# transformer.net
KiCad netlist of a schematic drawn in Altium Designer
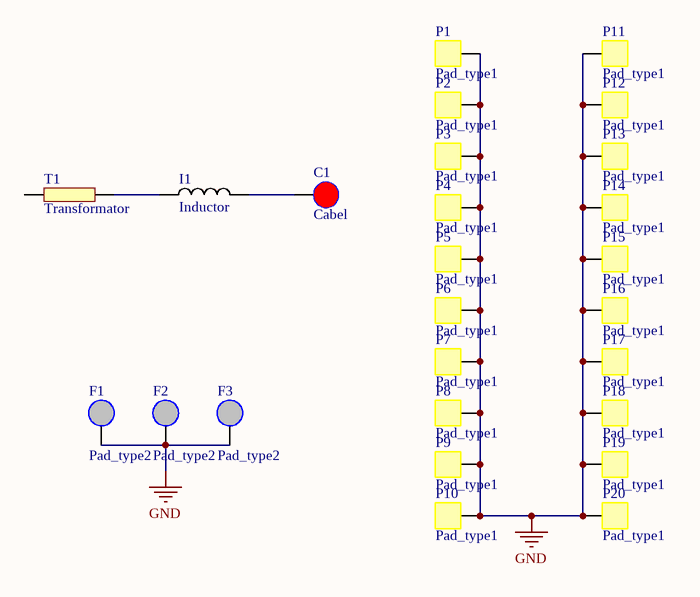
[diagram p0: transformer.SchDoc]

(export (version "E")
  (design (tool "Eeschema 10.0.6"))
  (components
    (comp (ref "C1")
      (value "Cabel")
      (footprint "transformerLib:pad_type3")
      (libsource (lib "transformerLib") (part "Cabel"))
    )
    (comp (ref "F1")
      (value "Pad_type2")
      (footprint "transformerLib:pad_type2")
      (libsource (lib "transformerLib") (part "Pad_type2"))
    )
    (comp (ref "F2")
      (value "Pad_type2")
      (footprint "transformerLib:pad_type2")
      (libsource (lib "transformerLib") (part "Pad_type2"))
    )
    (comp (ref "F3")
      (value "Pad_type2")
      (footprint "transformerLib:pad_type2")
      (libsource (lib "transformerLib") (part "Pad_type2"))
    )
    (comp (ref "I1")
      (value "Inductor")
      (footprint "transformerLib:Inductor")
      (libsource (lib "transformerLib") (part "Inductor"))
    )
    (comp (ref "P1")
      (value "Pad_type1")
      (footprint "transformerLib:pad_type1")
      (libsource (lib "transformerLib") (part "Pad_type1"))
    )
    (comp (ref "P2")
      (value "Pad_type1")
      (footprint "transformerLib:pad_type1")
      (libsource (lib "transformerLib") (part "Pad_type1"))
    )
    (comp (ref "P3")
      (value "Pad_type1")
      (footprint "transformerLib:pad_type1")
      (libsource (lib "transformerLib") (part "Pad_type1"))
    )
    (comp (ref "P4")
      (value "Pad_type1")
      (footprint "transformerLib:pad_type1")
      (libsource (lib "transformerLib") (part "Pad_type1"))
    )
    (comp (ref "P5")
      (value "Pad_type1")
      (footprint "transformerLib:pad_type1")
      (libsource (lib "transformerLib") (part "Pad_type1"))
    )
    (comp (ref "P6")
      (value "Pad_type1")
      (footprint "transformerLib:pad_type1")
      (libsource (lib "transformerLib") (part "Pad_type1"))
    )
    (comp (ref "P7")
      (value "Pad_type1")
      (footprint "transformerLib:pad_type1")
      (libsource (lib "transformerLib") (part "Pad_type1"))
    )
    (comp (ref "P8")
      (value "Pad_type1")
      (footprint "transformerLib:pad_type1")
      (libsource (lib "transformerLib") (part "Pad_type1"))
    )
    (comp (ref "P9")
      (value "Pad_type1")
      (footprint "transformerLib:pad_type1")
      (libsource (lib "transformerLib") (part "Pad_type1"))
    )
    (comp (ref "P10")
      (value "Pad_type1")
      (footprint "transformerLib:pad_type1")
      (libsource (lib "transformerLib") (part "Pad_type1"))
    )
    (comp (ref "P11")
      (value "Pad_type1")
      (footprint "transformerLib:pad_type1")
      (libsource (lib "") (part "Pad_type1_1"))
    )
    (comp (ref "P12")
      (value "Pad_type1")
      (footprint "transformerLib:pad_type1")
      (libsource (lib "") (part "Pad_type1_1"))
    )
    (comp (ref "P13")
      (value "Pad_type1")
      (footprint "transformerLib:pad_type1")
      (libsource (lib "") (part "Pad_type1_1"))
    )
    (comp (ref "P14")
      (value "Pad_type1")
      (footprint "transformerLib:pad_type1")
      (libsource (lib "") (part "Pad_type1_1"))
    )
    (comp (ref "P15")
      (value "Pad_type1")
      (footprint "transformerLib:pad_type1")
      (libsource (lib "") (part "Pad_type1_1"))
    )
    (comp (ref "P16")
      (value "Pad_type1")
      (footprint "transformerLib:pad_type1")
      (libsource (lib "") (part "Pad_type1_1"))
    )
    (comp (ref "P17")
      (value "Pad_type1")
      (footprint "transformerLib:pad_type1")
      (libsource (lib "") (part "Pad_type1_1"))
    )
    (comp (ref "P18")
      (value "Pad_type1")
      (footprint "transformerLib:pad_type1")
      (libsource (lib "") (part "Pad_type1_1"))
    )
    (comp (ref "P19")
      (value "Pad_type1")
      (footprint "transformerLib:pad_type1")
      (libsource (lib "") (part "Pad_type1_1"))
    )
    (comp (ref "P20")
      (value "Pad_type1")
      (footprint "transformerLib:pad_type1")
      (libsource (lib "") (part "Pad_type1_1"))
    )
    (comp (ref "T1")
      (value "Transformator")
      (footprint "transformerLib:tr_all")
      (libsource (lib "transformerLib") (part "Transformator"))
    )
  )
  (nets
    (net (code "1") (name "GND") (class "Default")
      (node (ref "F1") (pin "1") (pinfunction "1_1") (pintype "passive"))
      (node (ref "F2") (pin "1") (pinfunction "1_1") (pintype "passive"))
      (node (ref "F3") (pin "1") (pinfunction "1_1") (pintype "passive"))
      (node (ref "P1") (pin "1") (pinfunction "1_1") (pintype "passive"))
      (node (ref "P10") (pin "1") (pinfunction "1_1") (pintype "passive"))
      (node (ref "P11") (pin "1") (pinfunction "1_1") (pintype "passive"))
      (node (ref "P12") (pin "1") (pinfunction "1_1") (pintype "passive"))
      (node (ref "P13") (pin "1") (pinfunction "1_1") (pintype "passive"))
      (node (ref "P14") (pin "1") (pinfunction "1_1") (pintype "passive"))
      (node (ref "P15") (pin "1") (pinfunction "1_1") (pintype "passive"))
      (node (ref "P16") (pin "1") (pinfunction "1_1") (pintype "passive"))
      (node (ref "P17") (pin "1") (pinfunction "1_1") (pintype "passive"))
      (node (ref "P18") (pin "1") (pinfunction "1_1") (pintype "passive"))
      (node (ref "P19") (pin "1") (pinfunction "1_1") (pintype "passive"))
      (node (ref "P2") (pin "1") (pinfunction "1_1") (pintype "passive"))
      (node (ref "P20") (pin "1") (pinfunction "1_1") (pintype "passive"))
      (node (ref "P3") (pin "1") (pinfunction "1_1") (pintype "passive"))
      (node (ref "P4") (pin "1") (pinfunction "1_1") (pintype "passive"))
      (node (ref "P5") (pin "1") (pinfunction "1_1") (pintype "passive"))
      (node (ref "P6") (pin "1") (pinfunction "1_1") (pintype "passive"))
      (node (ref "P7") (pin "1") (pinfunction "1_1") (pintype "passive"))
      (node (ref "P8") (pin "1") (pinfunction "1_1") (pintype "passive"))
      (node (ref "P9") (pin "1") (pinfunction "1_1") (pintype "passive"))
    )
    (net (code "2") (name "Net-(C1-Pad1)") (class "Default")
      (node (ref "C1") (pin "1") (pinfunction "1_1") (pintype "passive"))
      (node (ref "I1") (pin "2") (pinfunction "2_2") (pintype "passive"))
    )
    (net (code "3") (name "Net-(I1-Pad1)") (class "Default")
      (node (ref "I1") (pin "1") (pinfunction "1_1") (pintype "passive"))
      (node (ref "T1") (pin "2") (pinfunction "2_2") (pintype "passive"))
    )
    (net (code "4") (name "unconnected-(T1-Pad1)") (class "Default")
      (node (ref "T1") (pin "1") (pinfunction "1_1") (pintype "passive"))
    )
  )
)
